# eeZee_microSD.net
KiCad netlist of a schematic drawn in EAGLE
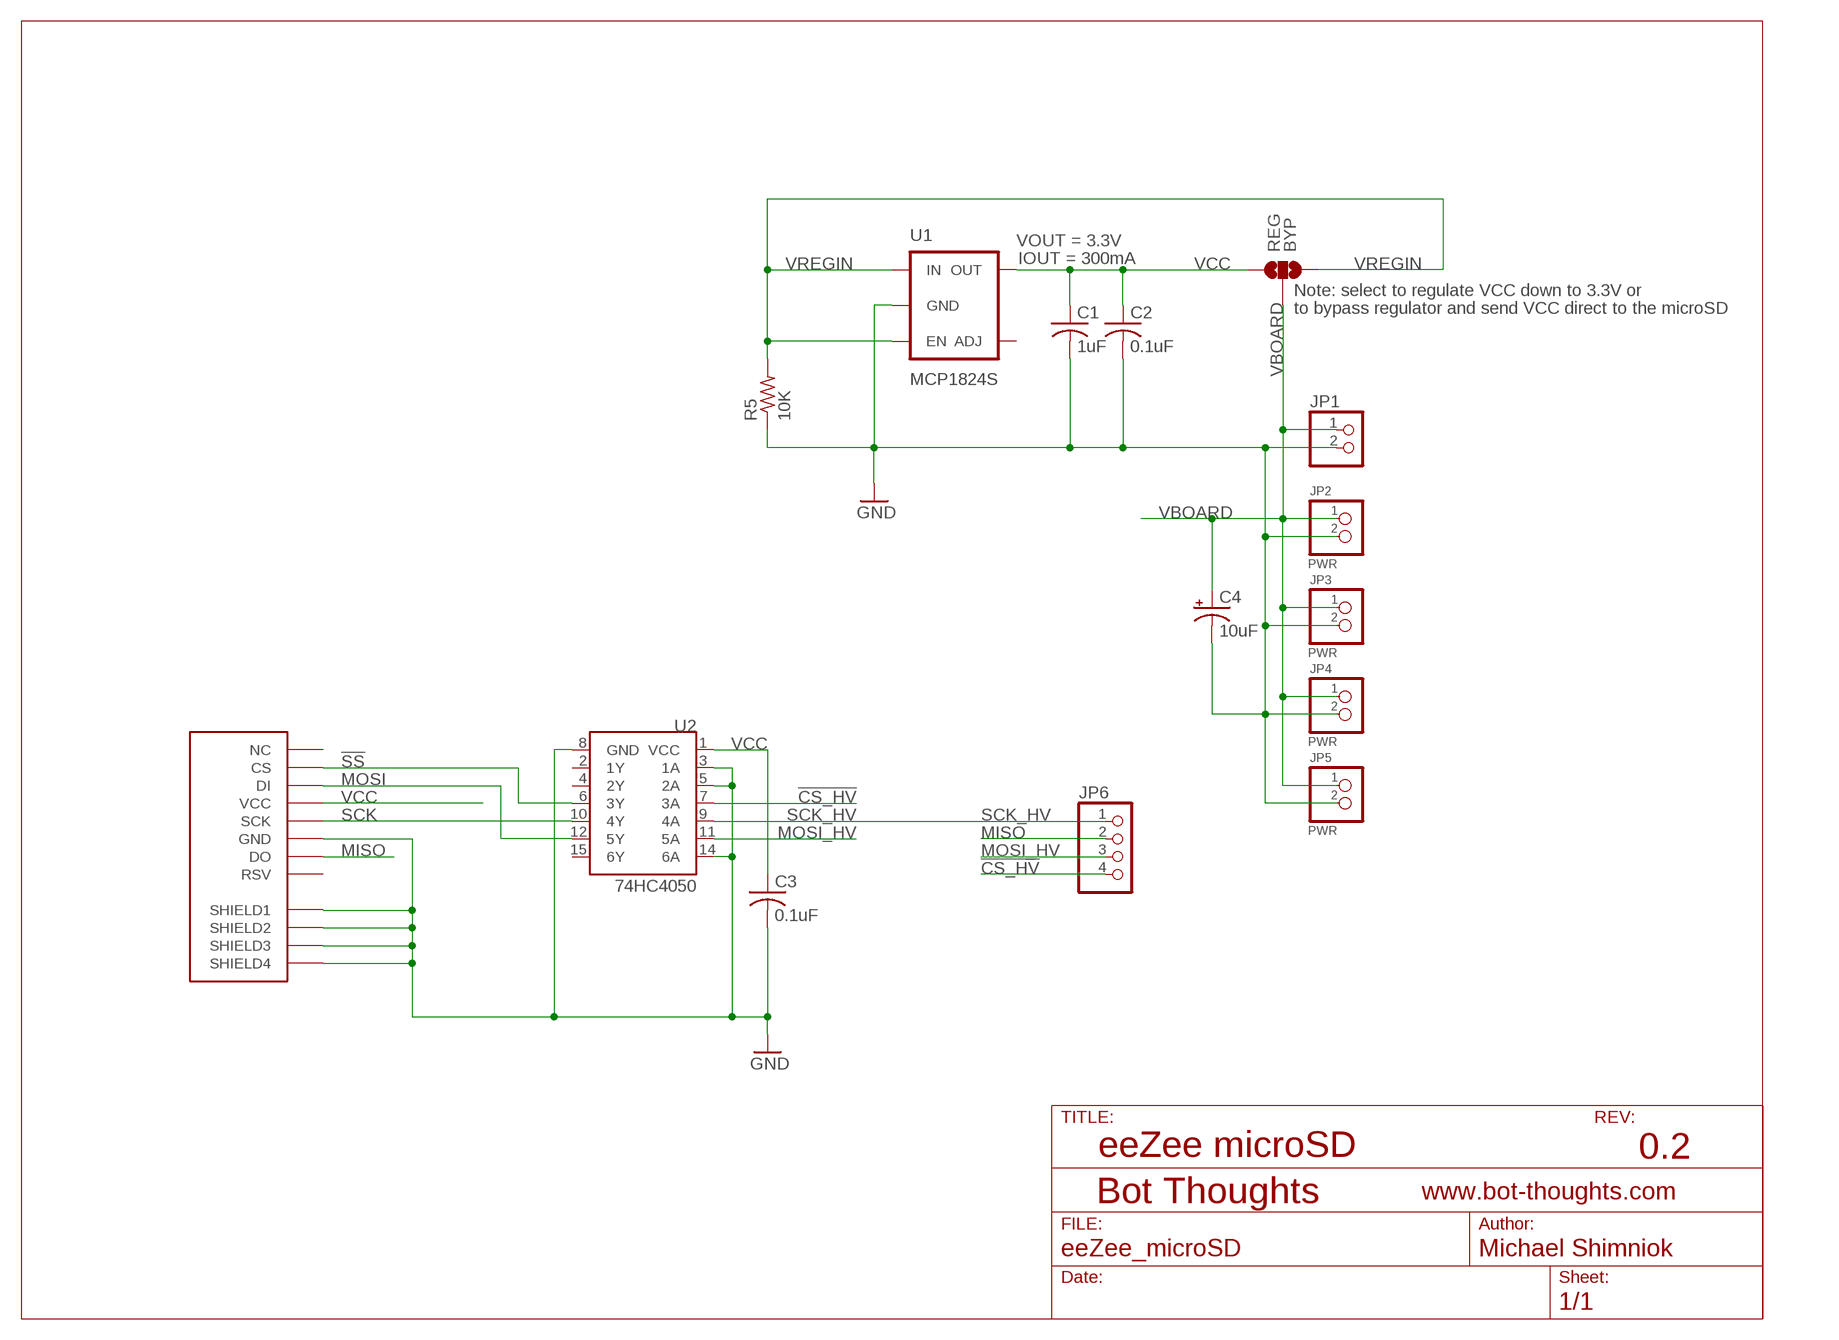
[diagram p0: schematic, sheet 1]

(export (version "E")
  (design (tool "Eeschema 10.0.6"))
  (components
    (comp (ref "C1")
      (value "1uF")
      (footprint "eagle-import:C0603")
      (fields (field (name "PARTNO") "LMK107B7105KA-T"))
      (libsource (lib "eagle-import") (part "C-USC0603"))
    )
    (comp (ref "C2")
      (value "0.1uF")
      (footprint "eagle-import:C0603")
      (fields (field (name "PARTNO") "LMK107B7105KA-T"))
      (libsource (lib "eagle-import") (part "C-USC0603"))
    )
    (comp (ref "C3")
      (value "0.1uF")
      (footprint "eagle-import:C0603")
      (fields (field (name "PARTNO") "LMK107B7105KA-T"))
      (libsource (lib "eagle-import") (part "C-USC0603"))
    )
    (comp (ref "C4")
      (value "10uF")
      (footprint "eagle-import:SMC_B")
      (fields (field (name "PARTNO") "LMK107B7105KA-T"))
      (libsource (lib "eagle-import") (part "CPOL-USSMCB"))
    )
    (comp (ref "JP1")
      (value "PINHD-1X02_2.54-S")
      (footprint "eagle-import:1X02-S")
      (libsource (lib "eagle-import") (part "PINHD-1X02_2.54-S"))
    )
    (comp (ref "JP2")
      (value "PWR")
      (footprint "eagle-import:BIGPIN-2")
      (libsource (lib "eagle-import") (part "PINHEAD-2BIG"))
    )
    (comp (ref "JP3")
      (value "PWR")
      (footprint "eagle-import:BIGPIN-2")
      (libsource (lib "eagle-import") (part "PINHEAD-2BIG"))
    )
    (comp (ref "JP4")
      (value "PWR")
      (footprint "eagle-import:BIGPIN-2")
      (libsource (lib "eagle-import") (part "PINHEAD-2BIG"))
    )
    (comp (ref "JP5")
      (value "PWR")
      (footprint "eagle-import:BIGPIN-2")
      (libsource (lib "eagle-import") (part "PINHEAD-2BIG"))
    )
    (comp (ref "JP6")
      (value "PINHD-1X04_2.54-S")
      (footprint "eagle-import:1X04-S")
      (libsource (lib "eagle-import") (part "PINHD-1X04_2.54-S"))
    )
    (comp (ref "R5")
      (value "10K")
      (footprint "eagle-import:R0603")
      (fields (field (name "PARTNO") "ERJ-3GEYJ103V"))
      (libsource (lib "eagle-import") (part "R-US_R0603"))
    )
    (comp (ref "REG")
      (value "BYP")
      (footprint "eagle-import:SJ_3")
      (libsource (lib "eagle-import") (part "SOLDERJUMPER_2WAYS"))
    )
    (comp (ref "U$1")
      (value "MICROSD_TFLASH")
      (footprint "eagle-import:TFLASH_CP-0000-086")
      (libsource (lib "eagle-import") (part "MICROSD_TFLASH"))
    )
    (comp (ref "U1")
      (value "MCP1824S")
      (footprint "eagle-import:SOT23-5")
      (fields
        (field (name "IOUT") "300mA")
        (field (name "PARTNO") "MCP1824ST-3302E/DB")
        (field (name "VOUT") "3.3V")
      )
      (libsource (lib "eagle-import") (part "MCP1824"))
    )
    (comp (ref "U2")
      (value "74HC4050")
      (footprint "eagle-import:SO016")
      (libsource (lib "eagle-import") (part "HEX_CONVERTER"))
    )
  )
  (nets
    (net (code "1") (name "/MISO") (class "Default")
      (node (ref "JP6") (pin "2") (pinfunction "2_2") (pintype "passive"))
      (node (ref "U$1") (pin "DO") (pinfunction "DO_DO") (pintype "bidirectional"))
    )
    (net (code "2") (name "/MOSI") (class "Default")
      (node (ref "U$1") (pin "DI") (pinfunction "DI_DI") (pintype "bidirectional"))
      (node (ref "U2") (pin "12") (pinfunction "5Y_12") (pintype "bidirectional"))
    )
    (net (code "3") (name "/MOSI_HV") (class "Default")
      (node (ref "JP6") (pin "3") (pinfunction "3_3") (pintype "passive"))
      (node (ref "U2") (pin "11") (pinfunction "5A_11") (pintype "bidirectional"))
    )
    (net (code "4") (name "/SCK") (class "Default")
      (node (ref "U$1") (pin "SCLK") (pinfunction "SCK_SCLK") (pintype "bidirectional"))
      (node (ref "U2") (pin "10") (pinfunction "4Y_10") (pintype "bidirectional"))
    )
    (net (code "5") (name "/SCK_HV") (class "Default")
      (node (ref "JP6") (pin "1") (pinfunction "1_1") (pintype "passive"))
      (node (ref "U2") (pin "9") (pinfunction "4A_9") (pintype "bidirectional"))
    )
    (net (code "6") (name "/VBOARD") (class "Default")
      (node (ref "C4") (pin "+") (pinfunction "+_+") (pintype "passive"))
      (node (ref "JP1") (pin "1") (pinfunction "1_1") (pintype "passive"))
      (node (ref "JP2") (pin "P$1") (pinfunction "1_P$1") (pintype "bidirectional"))
      (node (ref "JP3") (pin "P$1") (pinfunction "1_P$1") (pintype "bidirectional"))
      (node (ref "JP4") (pin "P$1") (pinfunction "1_P$1") (pintype "bidirectional"))
      (node (ref "JP5") (pin "P$1") (pinfunction "1_P$1") (pintype "bidirectional"))
      (node (ref "REG") (pin "2") (pinfunction "2_2") (pintype "passive"))
    )
    (net (code "7") (name "/VCC") (class "Default")
      (node (ref "C1") (pin "1") (pinfunction "1_1") (pintype "passive"))
      (node (ref "C2") (pin "1") (pinfunction "1_1") (pintype "passive"))
      (node (ref "C3") (pin "1") (pinfunction "1_1") (pintype "passive"))
      (node (ref "REG") (pin "1") (pinfunction "1_1") (pintype "passive"))
      (node (ref "U$1") (pin "VDD") (pinfunction "VCC_VDD") (pintype "bidirectional"))
      (node (ref "U1") (pin "5") (pinfunction "OUT_5") (pintype "passive"))
      (node (ref "U2") (pin "1") (pinfunction "VCC_1") (pintype "bidirectional"))
    )
    (net (code "8") (name "/VREGIN") (class "Default")
      (node (ref "R5") (pin "2") (pinfunction "2_2") (pintype "passive"))
      (node (ref "REG") (pin "3") (pinfunction "3_3") (pintype "passive"))
      (node (ref "U1") (pin "1") (pinfunction "IN_1") (pintype "input"))
      (node (ref "U1") (pin "3") (pinfunction "EN_3") (pintype "input"))
    )
    (net (code "9") (name "/~{CS_HV}") (class "Default")
      (node (ref "JP6") (pin "4") (pinfunction "4_4") (pintype "passive"))
      (node (ref "U2") (pin "7") (pinfunction "3A_7") (pintype "bidirectional"))
    )
    (net (code "10") (name "/~{SS}") (class "Default")
      (node (ref "U$1") (pin "CS") (pinfunction "CS_CS") (pintype "bidirectional"))
      (node (ref "U2") (pin "6") (pinfunction "3Y_6") (pintype "bidirectional"))
    )
    (net (code "11") (name "GND") (class "Default")
      (node (ref "C1") (pin "2") (pinfunction "2_2") (pintype "passive"))
      (node (ref "C2") (pin "2") (pinfunction "2_2") (pintype "passive"))
      (node (ref "C3") (pin "2") (pinfunction "2_2") (pintype "passive"))
      (node (ref "C4") (pin "-") (pinfunction "-_-") (pintype "passive"))
      (node (ref "JP1") (pin "2") (pinfunction "2_2") (pintype "passive"))
      (node (ref "JP2") (pin "P$2") (pinfunction "2_P$2") (pintype "bidirectional"))
      (node (ref "JP3") (pin "P$2") (pinfunction "2_P$2") (pintype "bidirectional"))
      (node (ref "JP4") (pin "P$2") (pinfunction "2_P$2") (pintype "bidirectional"))
      (node (ref "JP5") (pin "P$2") (pinfunction "2_P$2") (pintype "bidirectional"))
      (node (ref "R5") (pin "1") (pinfunction "1_1") (pintype "passive"))
      (node (ref "U$1") (pin "GND") (pinfunction "GND_GND") (pintype "bidirectional"))
      (node (ref "U$1") (pin "SHIELD1") (pinfunction "SHIELD1_SHIELD1") (pintype "bidirectional"))
      (node (ref "U$1") (pin "SHIELD2") (pinfunction "SHIELD2_SHIELD2") (pintype "bidirectional"))
      (node (ref "U$1") (pin "SHIELD3") (pinfunction "SHIELD3_SHIELD3") (pintype "bidirectional"))
      (node (ref "U$1") (pin "SHIELD4") (pinfunction "SHIELD4_SHIELD4") (pintype "bidirectional"))
      (node (ref "U1") (pin "2") (pinfunction "GND_2") (pintype "input"))
      (node (ref "U2") (pin "14") (pinfunction "6A_14") (pintype "bidirectional"))
      (node (ref "U2") (pin "3") (pinfunction "1A_3") (pintype "bidirectional"))
      (node (ref "U2") (pin "5") (pinfunction "2A_5") (pintype "bidirectional"))
      (node (ref "U2") (pin "8") (pinfunction "GND_8") (pintype "bidirectional"))
    )
    (net (code "12") (name "unconnected-(U$1-PadNC)") (class "Default")
      (node (ref "U$1") (pin "NC") (pinfunction "NC_NC") (pintype "bidirectional"))
    )
    (net (code "13") (name "unconnected-(U$1-PadRSV)") (class "Default")
      (node (ref "U$1") (pin "RSV") (pinfunction "RSV_RSV") (pintype "bidirectional"))
    )
    (net (code "14") (name "unconnected-(U1-ADJ-Pad4)") (class "Default")
      (node (ref "U1") (pin "4") (pinfunction "ADJ_4") (pintype "input"))
    )
    (net (code "15") (name "unconnected-(U2-1Y-Pad2)") (class "Default")
      (node (ref "U2") (pin "2") (pinfunction "1Y_2") (pintype "bidirectional"))
    )
    (net (code "16") (name "unconnected-(U2-2Y-Pad4)") (class "Default")
      (node (ref "U2") (pin "4") (pinfunction "2Y_4") (pintype "bidirectional"))
    )
    (net (code "17") (name "unconnected-(U2-6Y-Pad15)") (class "Default")
      (node (ref "U2") (pin "15") (pinfunction "6Y_15") (pintype "bidirectional"))
    )
  )
)
